# sheet1.net
KiCad netlist of a schematic drawn in Altium Designer
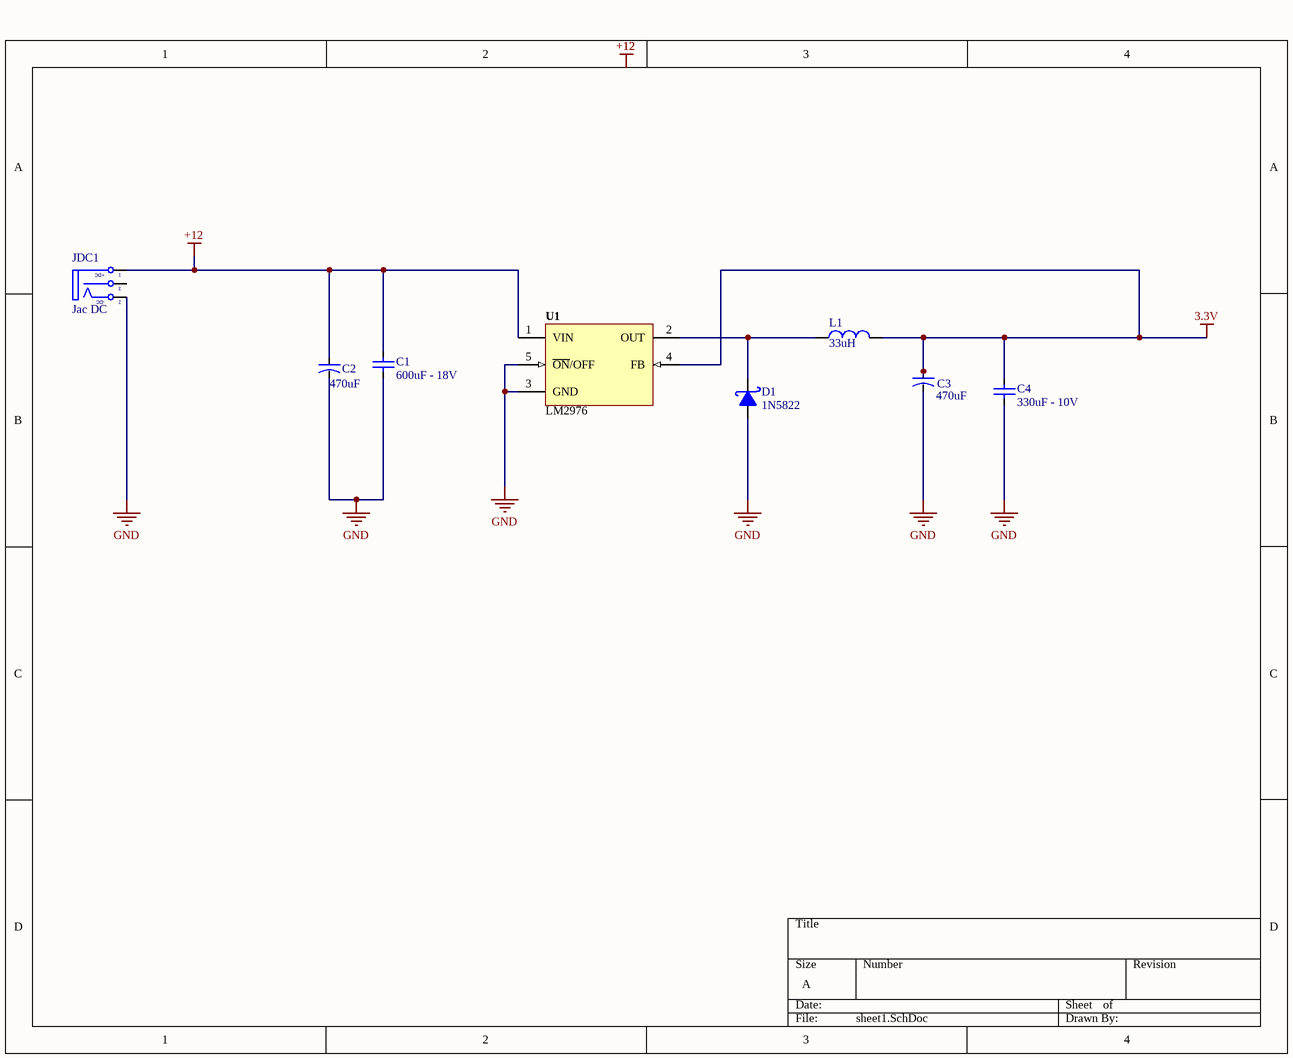
[diagram p0: sheet1.SchDoc]

(export (version "E")
  (design (tool "Eeschema 10.0.6"))
  (components
    (comp (ref "C1")
      (value "600uF - 18V")
      (footprint "103/2KV")
      (description "Capacitor Ceramic 2KV")
      (fields (field (name "PUBLISHER") "Altium Limited"))
      (libsource (lib "My-Library") (part "Cap2KV"))
    )
    (comp (ref "C2")
      (value "470uF")
      (footprint "CA-ALU-2.54")
      (description "Capacitor (Semiconductor SIM Model)")
      (fields (field (name "PUBLISHER") "Altium Limited"))
      (libsource (lib "My-Library") (part "CAP-ALU-DIP"))
    )
    (comp (ref "C3")
      (value "470uF")
      (footprint "CAP-ALU-SMD-4.5x5x1.4")
      (description "Polarized Capacitor (Axial)")
      (fields (field (name "PUBLISHER") "Altium Limited"))
      (libsource (lib "My-Library") (part "CAP-ALU-SMD"))
    )
    (comp (ref "C4")
      (value "330uF - 10V")
      (footprint "103/2KV")
      (description "Capacitor Ceramic 2KV")
      (fields (field (name "PUBLISHER") "Altium Limited"))
      (libsource (lib "My-Library") (part "Cap2KV"))
    )
    (comp (ref "D1")
      (value "1N5822")
      (footprint "DIO-SMD-123")
      (description "Schottky Rectifiers")
      (libsource (lib "My-Library") (part "1N5822"))
    )
    (comp (ref "JDC1")
      (value "Jac DC")
      (footprint "DC-IN")
      (description "Jac DC input")
      (libsource (lib "My-Library") (part "DCIN"))
    )
    (comp (ref "L1")
      (value "33uH")
      (footprint "L-SMD-M-12x10")
      (description "Inductor")
      (libsource (lib "My-Library") (part "Inductor"))
    )
    (comp (ref "U1") (value "LM2976") (footprint "TO263") (libsource (lib "My-Library") (part "LM2596")))
  )
  (nets
    (net (code "1") (name "+12") (class "Default")
      (node (ref "C1") (pin "2") (pinfunction "2_2") (pintype "passive"))
      (node (ref "C2") (pin "1") (pinfunction "1_1") (pintype "passive"))
      (node (ref "JDC1") (pin "1") (pinfunction "T_1") (pintype "passive"))
      (node (ref "U1") (pin "1") (pinfunction "VIN_1") (pintype "power_in"))
    )
    (net (code "2") (name "3.3V") (class "Default")
      (node (ref "C3") (pin "1") (pinfunction "1_1") (pintype "passive"))
      (node (ref "C4") (pin "2") (pinfunction "2_2") (pintype "passive"))
      (node (ref "L1") (pin "2") (pinfunction "2_2") (pintype "passive"))
      (node (ref "U1") (pin "4") (pinfunction "FB_4") (pintype "input"))
    )
    (net (code "3") (name "GND") (class "Default")
      (node (ref "C1") (pin "1") (pinfunction "1_1") (pintype "passive"))
      (node (ref "C2") (pin "2") (pinfunction "2_2") (pintype "passive"))
      (node (ref "C3") (pin "2") (pinfunction "2_2") (pintype "passive"))
      (node (ref "C4") (pin "1") (pinfunction "1_1") (pintype "passive"))
      (node (ref "D1") (pin "1") (pinfunction "A_1") (pintype "passive"))
      (node (ref "JDC1") (pin "2") (pinfunction "TN_2") (pintype "passive"))
      (node (ref "U1") (pin "3") (pinfunction "GND_3") (pintype "power_in"))
      (node (ref "U1") (pin "5") (pinfunction "~{ON}/OFF_5") (pintype "input"))
    )
    (net (code "4") (name "Net-(D1-K)") (class "Default")
      (node (ref "D1") (pin "2") (pinfunction "K_2") (pintype "passive"))
      (node (ref "L1") (pin "1") (pinfunction "1_1") (pintype "passive"))
      (node (ref "U1") (pin "2") (pinfunction "OUT_2") (pintype "power_in"))
    )
    (net (code "5") (name "unconnected-(JDC1-S-Pad3)") (class "Default")
      (node (ref "JDC1") (pin "3") (pinfunction "S_3") (pintype "power_in"))
    )
  )
)
